# Sheet2.net
KiCad netlist of a schematic drawn in Altium Designer
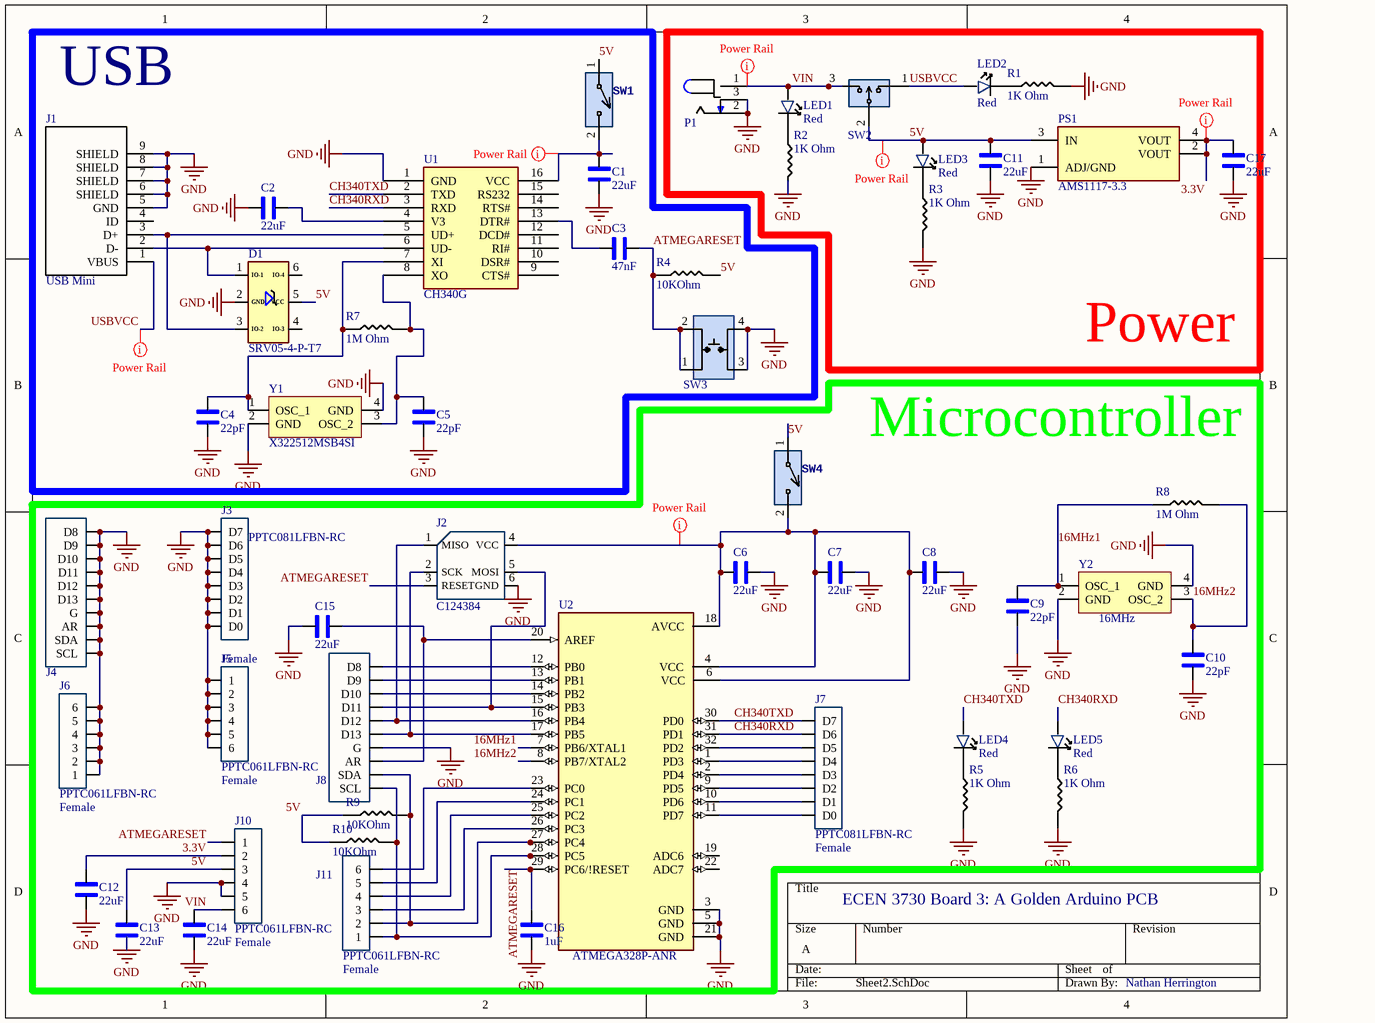
[diagram p0: Sheet2.SchDoc]

(export (version "E")
  (design (tool "Eeschema 10.0.6"))
  (components
    (comp (ref "C1")
      (value "22uF")
      (footprint "1206_Passive_Capacitor")
      (description "22uF ±10% 25V X5R 1206 Multilayer Ceramic Capacitors MLCC - SMD/SMT RoHS")
      (fields (field (name "MFR PART #") "CL31A226KAHNNNE") (field (name "LCSC PART#") "C12891"))
      (libsource (lib "ECEN5730Lib_2023_05_DS") (part "C_22uF_1206"))
    )
    (comp (ref "C2")
      (value "22uF")
      (footprint "1206_Passive_Capacitor")
      (description "22uF ±10% 25V X5R 1206 Multilayer Ceramic Capacitors MLCC - SMD/SMT RoHS")
      (fields (field (name "MFR PART #") "CL31A226KAHNNNE") (field (name "LCSC PART#") "C12891"))
      (libsource (lib "ECEN5730Lib_2023_05_DS") (part "C_22uF_1206"))
    )
    (comp (ref "C3")
      (value "47nF")
      (footprint "1206_Passive_Capacitor")
      (description "47nF ±5% 50V C0G 1206 Multilayer Ceramic Capacitors MLCC - SMD/SMT RoHS")
      (fields (field (name "LCSC PART#") "C21812") (field (name "MFR PART #") "GRM31M5C1H473JA01L"))
      (libsource (lib "ECEN5730Lib_2023_05_DS") (part "C_47nF_1206"))
    )
    (comp (ref "C4")
      (value "22pF")
      (footprint "1206_Passive_Capacitor")
      (description "22pF ±5% 1kV C0G 1206 Multilayer Ceramic Capacitors MLCC - SMD/SMT RoHS")
      (fields (field (name "MFR PART #") "CC1206JKNPOCBN220") (field (name "LCSC PART#") "C107174"))
      (libsource (lib "ECEN5730Lib_2023_05_DS") (part "C_22pF_1206"))
    )
    (comp (ref "C5")
      (value "22pF")
      (footprint "1206_Passive_Capacitor")
      (description "22pF ±5% 1kV C0G 1206 Multilayer Ceramic Capacitors MLCC - SMD/SMT RoHS")
      (fields (field (name "MFR PART #") "CC1206JKNPOCBN220") (field (name "LCSC PART#") "C107174"))
      (libsource (lib "ECEN5730Lib_2023_05_DS") (part "C_22pF_1206"))
    )
    (comp (ref "C6")
      (value "22uF")
      (footprint "1206_Passive_Capacitor")
      (description "22uF ±10% 25V X5R 1206 Multilayer Ceramic Capacitors MLCC - SMD/SMT RoHS")
      (fields (field (name "MFR PART #") "CL31A226KAHNNNE") (field (name "LCSC PART#") "C12891"))
      (libsource (lib "ECEN5730Lib_2023_05_DS") (part "C_22uF_1206"))
    )
    (comp (ref "C7")
      (value "22uF")
      (footprint "1206_Passive_Capacitor")
      (description "22uF ±10% 25V X5R 1206 Multilayer Ceramic Capacitors MLCC - SMD/SMT RoHS")
      (fields (field (name "MFR PART #") "CL31A226KAHNNNE") (field (name "LCSC PART#") "C12891"))
      (libsource (lib "ECEN5730Lib_2023_05_DS") (part "C_22uF_1206"))
    )
    (comp (ref "C8")
      (value "22uF")
      (footprint "1206_Passive_Capacitor")
      (description "22uF ±10% 25V X5R 1206 Multilayer Ceramic Capacitors MLCC - SMD/SMT RoHS")
      (fields (field (name "MFR PART #") "CL31A226KAHNNNE") (field (name "LCSC PART#") "C12891"))
      (libsource (lib "ECEN5730Lib_2023_05_DS") (part "C_22uF_1206"))
    )
    (comp (ref "C9")
      (value "22pF")
      (footprint "1206_Passive_Capacitor")
      (description "22pF ±5% 1kV C0G 1206 Multilayer Ceramic Capacitors MLCC - SMD/SMT RoHS")
      (fields (field (name "MFR PART #") "CC1206JKNPOCBN220") (field (name "LCSC PART#") "C107174"))
      (libsource (lib "ECEN5730Lib_2023_05_DS") (part "C_22pF_1206"))
    )
    (comp (ref "C10")
      (value "22pF")
      (footprint "1206_Passive_Capacitor")
      (description "22pF ±5% 1kV C0G 1206 Multilayer Ceramic Capacitors MLCC - SMD/SMT RoHS")
      (fields (field (name "MFR PART #") "CC1206JKNPOCBN220") (field (name "LCSC PART#") "C107174"))
      (libsource (lib "ECEN5730Lib_2023_05_DS") (part "C_22pF_1206"))
    )
    (comp (ref "C11")
      (value "22uF")
      (footprint "1206_Passive_Capacitor")
      (description "22uF ±10% 25V X5R 1206 Multilayer Ceramic Capacitors MLCC - SMD/SMT RoHS")
      (fields (field (name "MFR PART #") "CL31A226KAHNNNE") (field (name "LCSC PART#") "C12891"))
      (libsource (lib "ECEN5730Lib_2023_05_DS") (part "C_22uF_1206"))
    )
    (comp (ref "C12")
      (value "22uF")
      (footprint "1206_Passive_Capacitor")
      (description "22uF ±10% 25V X5R 1206 Multilayer Ceramic Capacitors MLCC - SMD/SMT RoHS")
      (fields (field (name "MFR PART #") "CL31A226KAHNNNE") (field (name "LCSC PART#") "C12891"))
      (libsource (lib "ECEN5730Lib_2023_05_DS") (part "C_22uF_1206"))
    )
    (comp (ref "C13")
      (value "22uF")
      (footprint "1206_Passive_Capacitor")
      (description "22uF ±10% 25V X5R 1206 Multilayer Ceramic Capacitors MLCC - SMD/SMT RoHS")
      (fields (field (name "MFR PART #") "CL31A226KAHNNNE") (field (name "LCSC PART#") "C12891"))
      (libsource (lib "ECEN5730Lib_2023_05_DS") (part "C_22uF_1206"))
    )
    (comp (ref "C14")
      (value "22uF")
      (footprint "1206_Passive_Capacitor")
      (description "22uF ±10% 25V X5R 1206 Multilayer Ceramic Capacitors MLCC - SMD/SMT RoHS")
      (fields (field (name "MFR PART #") "CL31A226KAHNNNE") (field (name "LCSC PART#") "C12891"))
      (libsource (lib "ECEN5730Lib_2023_05_DS") (part "C_22uF_1206"))
    )
    (comp (ref "C15")
      (value "22uF")
      (footprint "1206_Passive_Capacitor")
      (description "22uF ±10% 25V X5R 1206 Multilayer Ceramic Capacitors MLCC - SMD/SMT RoHS")
      (fields (field (name "MFR PART #") "CL31A226KAHNNNE") (field (name "LCSC PART#") "C12891"))
      (libsource (lib "ECEN5730Lib_2023_05_DS") (part "C_22uF_1206"))
    )
    (comp (ref "C16")
      (value "1uF")
      (footprint "1206_Passive_Capacitor")
      (description "MULTILAYER CERAMIC CAPACITORS MLCC - SMD/SMT 1UF 50V 1206 ROHS")
      (fields (field (name "MFR PART #") "CL31B105KBHNNNE") (field (name "LCSC PART#") "C1848"))
      (libsource (lib "ECEN5730Lib_2023_05_DS") (part "C_1uF_1206"))
    )
    (comp (ref "C17")
      (value "22uF")
      (footprint "1206_Passive_Capacitor")
      (description "22uF ±10% 25V X5R 1206 Multilayer Ceramic Capacitors MLCC - SMD/SMT RoHS")
      (fields (field (name "MFR PART #") "CL31A226KAHNNNE") (field (name "LCSC PART#") "C12891"))
      (libsource (lib "ECEN5730Lib_2023_05_DS") (part "C_22uF_1206"))
    )
    (comp (ref "D1")
      (value "SRV05-4-P-T7")
      (footprint "TVS")
      (description "TVS SOT-23-6 ROHS")
      (fields (field (name "LCSC PART#") "C85364"))
      (libsource (lib "ECEN5730Lib_2023_05_DS") (part "D_TVS_Diode"))
    )
    (comp (ref "J1")
      (value "USB Mini")
      (footprint "USB_MINI_B")
      (description "Through Hole USB Connectors RoHS")
      (fields (field (name "LCSC PART#") "C46398") (field (name "MFR PART #") "920-462A2021D10102"))
      (libsource (lib "ECEN5730Lib_2023_05_DS") (part "J_USB_B_Mini"))
    )
    (comp (ref "J2")
      (value "NRPN032PAEN-RC")
      (footprint "ICSP")
      (description "Connector Header Through Hole 6 position 0.079\" (2.00mm)")
      (fields (field (name "LCSC PART#") "C124384"))
      (libsource (lib "ECEN5730Lib_2023_05_DS") (part "J_ICSP"))
    )
    (comp (ref "J3")
      (value "PPTC081LFBN-RC")
      (footprint "8_PIN_ARD-DIG_100MIL")
      (description "8 Position Header Connector 0.100\" (2.54mm) Through Hole Tin")
      (fields (field (name "LCSC PART#") "C27438") (field (name "ALTIUM_VALUE") "Female"))
      (libsource (lib "ECEN5730Lib_2023_05_DS") (part "JF_8_PIN_FEMA_ARD-Dig"))
    )
    (comp (ref "J4")
      (value "PPTC101LFBN-RC")
      (footprint "10_PIN_ARDUINO_100MIL")
      (description "10 Position Header Connector 0.100\" (2.54mm) Through Hole Tin")
      (fields (field (name "LCSC PART#") "C225507"))
      (libsource (lib "ECEN5730Lib_2023_05_DS") (part "JF_10_PIN_FEMA_ARDUINO"))
    )
    (comp (ref "J5")
      (value "PPTC061LFBN-RC")
      (footprint "6_PIN_100MIL -Female")
      (description "6 Position Header Connector 0.100\" (2.54mm) Through Hole Tin")
      (fields (field (name "LCSC PART#") "C40877") (field (name "ALTIUM_VALUE") "Female"))
      (libsource (lib "ECEN5730Lib_2023_05_DS") (part "JF_6_PIN_FEMALE"))
    )
    (comp (ref "J6")
      (value "PPTC061LFBN-RC")
      (footprint "6_PIN_100MIL -Female")
      (description "6 Position Header Connector 0.100\" (2.54mm) Through Hole Tin")
      (fields (field (name "LCSC PART#") "C40877") (field (name "ALTIUM_VALUE") "Female"))
      (libsource (lib "") (part "JF_6_PIN_FEMALE_1"))
    )
    (comp (ref "J7")
      (value "PPTC081LFBN-RC")
      (footprint "8_PIN_ARD-DIG_100MIL")
      (description "8 Position Header Connector 0.100\" (2.54mm) Through Hole Tin")
      (fields (field (name "LCSC PART#") "C27438") (field (name "ALTIUM_VALUE") "Female"))
      (libsource (lib "ECEN5730Lib_2023_05_DS") (part "JF_8_PIN_FEMA_ARD-Dig"))
    )
    (comp (ref "J8")
      (value "PPTC101LFBN-RC")
      (footprint "10_PIN_ARDUINO_100MIL")
      (description "10 Position Header Connector 0.100\" (2.54mm) Through Hole Tin")
      (fields (field (name "LCSC PART#") "C225507"))
      (libsource (lib "ECEN5730Lib_2023_05_DS") (part "JF_10_PIN_FEMA_ARDUINO"))
    )
    (comp (ref "J10")
      (value "PPTC061LFBN-RC")
      (footprint "6_PIN_100MIL -Female")
      (description "6 Position Header Connector 0.100\" (2.54mm) Through Hole Tin")
      (fields (field (name "LCSC PART#") "C40877") (field (name "ALTIUM_VALUE") "Female"))
      (libsource (lib "ECEN5730Lib_2023_05_DS") (part "JF_6_PIN_FEMALE"))
    )
    (comp (ref "J11")
      (value "PPTC061LFBN-RC")
      (footprint "6_PIN_100MIL -Female")
      (description "6 Position Header Connector 0.100\" (2.54mm) Through Hole Tin")
      (fields (field (name "LCSC PART#") "C40877") (field (name "ALTIUM_VALUE") "Female"))
      (libsource (lib "") (part "JF_6_PIN_FEMALE_1"))
    )
    (comp (ref "LED1")
      (value "Red")
      (footprint "LED_1206")
      (description "Red 621~631nm 1206 Light Emitting Diodes (LED) RoHS")
      (fields (field (name "MFR PART #") "15-21/R6C-FQ1R1B/2T") (field (name "LCSC PART#") "C93133"))
      (libsource (lib "ECEN5730Lib_2023_05_DS") (part "LED_RED_1206"))
    )
    (comp (ref "LED2")
      (value "Red")
      (footprint "LED_1206")
      (description "Red 621~631nm 1206 Light Emitting Diodes (LED) RoHS")
      (fields (field (name "MFR PART #") "15-21/R6C-FQ1R1B/2T") (field (name "LCSC PART#") "C93133"))
      (libsource (lib "ECEN5730Lib_2023_05_DS") (part "LED_RED_1206"))
    )
    (comp (ref "LED3")
      (value "Red")
      (footprint "LED_1206")
      (description "Red 621~631nm 1206 Light Emitting Diodes (LED) RoHS")
      (fields (field (name "MFR PART #") "15-21/R6C-FQ1R1B/2T") (field (name "LCSC PART#") "C93133"))
      (libsource (lib "ECEN5730Lib_2023_05_DS") (part "LED_RED_1206"))
    )
    (comp (ref "LED4")
      (value "Red")
      (footprint "LED_1206")
      (description "Red 621~631nm 1206 Light Emitting Diodes (LED) RoHS")
      (fields (field (name "MFR PART #") "15-21/R6C-FQ1R1B/2T") (field (name "LCSC PART#") "C93133"))
      (libsource (lib "ECEN5730Lib_2023_05_DS") (part "LED_RED_1206"))
    )
    (comp (ref "LED5")
      (value "Red")
      (footprint "LED_1206")
      (description "Red 621~631nm 1206 Light Emitting Diodes (LED) RoHS")
      (fields (field (name "MFR PART #") "15-21/R6C-FQ1R1B/2T") (field (name "LCSC PART#") "C93133"))
      (libsource (lib "ECEN5730Lib_2023_05_DS") (part "LED_RED_1206"))
    )
    (comp (ref "P1")
      (value "Power Jack")
      (footprint "Power_Jack")
      (description "Power Barrel Connector Jack 2.10mm ID (0.083\"), 5.50mm OD (0.217\") Through Hole, Right Angle")
      (fields (field (name "MFR PART #") "PJ-102A") (field (name "LCSC PART#") "C136744"))
      (libsource (lib "ECEN5730Lib_2023_05_DS") (part "P_Power Jack"))
    )
    (comp (ref "PS1")
      (value "AMS1117-3.3")
      (footprint "LDO")
      (description "LOW DROPOUT REGULATORS(LDO) POSITIVE FIXED 1.3V @ 800MA 15V 3.3V 1A SOT-223 ROHS")
      (fields (field (name "LCSC PART#") "C6186"))
      (libsource (lib "ECEN5730Lib_2023_05_DS") (part "PS_AMS_LDO_3v3"))
    )
    (comp (ref "R1")
      (value "1K Ohm")
      (footprint "1206_Passive_Resitor")
      (description "CHIP RESISTOR - SURFACE MOUNT 1KOHMS ±1% 1/4W 1206 ROHS")
      (fields (field (name "MFR PART #") "RNCP1206FTD1K00CT") (field (name "LCSC PART#") "C4410"))
      (libsource (lib "ECEN5730Lib_2023_05_DS") (part "R_1K_1206"))
    )
    (comp (ref "R2")
      (value "1K Ohm")
      (footprint "1206_Passive_Resitor")
      (description "CHIP RESISTOR - SURFACE MOUNT 1KOHMS ±1% 1/4W 1206 ROHS")
      (fields (field (name "MFR PART #") "RNCP1206FTD1K00CT") (field (name "LCSC PART#") "C4410"))
      (libsource (lib "ECEN5730Lib_2023_05_DS") (part "R_1K_1206"))
    )
    (comp (ref "R3")
      (value "1K Ohm")
      (footprint "1206_Passive_Resitor")
      (description "CHIP RESISTOR - SURFACE MOUNT 1KOHMS ±1% 1/4W 1206 ROHS")
      (fields (field (name "MFR PART #") "RNCP1206FTD1K00CT") (field (name "LCSC PART#") "C4410"))
      (libsource (lib "ECEN5730Lib_2023_05_DS") (part "R_1K_1206"))
    )
    (comp (ref "R4")
      (value "10KOhm")
      (footprint "1206_Passive_Resitor")
      (description "10 kOhms ±5% 0.25W, 1/4W Chip Resistor 1206 (3216 Metric) Automotive AEC-Q200 Thick Film")
      (fields (field (name "MFR PART #") "RMCF1206FT10K0") (field (name "LCSC PART#") "C17902"))
      (libsource (lib "ECEN5730Lib_2023_05_DS") (part "R_10KOhm_1206"))
    )
    (comp (ref "R5")
      (value "1K Ohm")
      (footprint "1206_Passive_Resitor")
      (description "CHIP RESISTOR - SURFACE MOUNT 1KOHMS ±1% 1/4W 1206 ROHS")
      (fields (field (name "MFR PART #") "RNCP1206FTD1K00CT") (field (name "LCSC PART#") "C4410"))
      (libsource (lib "ECEN5730Lib_2023_05_DS") (part "R_1K_1206"))
    )
    (comp (ref "R6")
      (value "1K Ohm")
      (footprint "1206_Passive_Resitor")
      (description "CHIP RESISTOR - SURFACE MOUNT 1KOHMS ±1% 1/4W 1206 ROHS")
      (fields (field (name "MFR PART #") "RNCP1206FTD1K00CT") (field (name "LCSC PART#") "C4410"))
      (libsource (lib "ECEN5730Lib_2023_05_DS") (part "R_1K_1206"))
    )
    (comp (ref "R7")
      (value "1M Ohm")
      (footprint "1206_Passive_Resitor")
      (description "CHIP RESISTOR - SURFACE MOUNT 1MOHMS ±1% 1/4W 1206 ROHS")
      (fields (field (name "MFR PART #") "RMCF1206JT1M00") (field (name "LCSC PART#") "C17927"))
      (libsource (lib "ECEN5730Lib_2023_05_DS") (part "R_1M_1206"))
    )
    (comp (ref "R8")
      (value "1M Ohm")
      (footprint "1206_Passive_Resitor")
      (description "CHIP RESISTOR - SURFACE MOUNT 1MOHMS ±1% 1/4W 1206 ROHS")
      (fields (field (name "MFR PART #") "RMCF1206JT1M00") (field (name "LCSC PART#") "C17927"))
      (libsource (lib "ECEN5730Lib_2023_05_DS") (part "R_1M_1206"))
    )
    (comp (ref "R9")
      (value "10KOhm")
      (footprint "1206_Passive_Resitor")
      (description "10 kOhms ±5% 0.25W, 1/4W Chip Resistor 1206 (3216 Metric) Automotive AEC-Q200 Thick Film")
      (fields (field (name "MFR PART #") "RMCF1206FT10K0") (field (name "LCSC PART#") "C17902"))
      (libsource (lib "ECEN5730Lib_2023_05_DS") (part "R_10KOhm_1206"))
    )
    (comp (ref "R10")
      (value "10KOhm")
      (footprint "1206_Passive_Resitor")
      (description "10 kOhms ±5% 0.25W, 1/4W Chip Resistor 1206 (3216 Metric) Automotive AEC-Q200 Thick Film")
      (fields (field (name "MFR PART #") "RMCF1206FT10K0") (field (name "LCSC PART#") "C17902"))
      (libsource (lib "ECEN5730Lib_2023_05_DS") (part "R_10KOhm_1206"))
    )
    (comp (ref "SW1")
      (value "SW_2Pin_100mil_Switch")
      (footprint "2Pin-Header-Conn")
      (description "2Pin Header")
      (fields (field (name "LCSC PART#") "C124375"))
      (libsource (lib "ECEN5730Lib_2023_05_DS") (part "SW_2Pin_100mil_Switch"))
    )
    (comp (ref "SW2")
      (value "PREC003SAAN-RC")
      (footprint "3_PIN_100mil")
      (description "Connector Header Through Hole 3 position 0.100\" (2.54mm)")
      (fields (field (name "LCSC PART#") "C49257"))
      (libsource (lib "ECEN5730Lib_2023_05_DS") (part "SW_3Pin_100mil_Switch"))
    )
    (comp (ref "SW3")
      (value "TL3305AF160QG")
      (footprint "Switch_JLC")
      (description "Tactile Switch SPST-NO Top Actuated Surface Mount")
      (fields (field (name "MFR PART #") "KH-4.5X4.5X4.3H-STM") (field (name "LCSC PART#") "C2837550"))
      (libsource (lib "ECEN5730Lib_2023_05_DS") (part "SW_Push_Button_JLC"))
    )
    (comp (ref "SW4")
      (value "SW_2Pin_100mil_Switch")
      (footprint "2Pin-Header-Conn")
      (description "2Pin Header")
      (fields (field (name "LCSC PART#") "C124375"))
      (libsource (lib "ECEN5730Lib_2023_05_DS") (part "SW_2Pin_100mil_Switch"))
    )
    (comp (ref "U1")
      (value "CH340G")
      (footprint "USB to serial")
      (description "Transceiver USB 2.0 2Mbps SOP-16_150mil USB ICs RoHS")
      (fields (field (name "LCSC PART#") "C14267"))
      (libsource (lib "ECEN5730Lib_2023_05_DS") (part "U_USBtoSerial"))
    )
    (comp (ref "U2")
      (value "ATMEGA328P-ANR")
      (footprint "ATMega328P")
      (description "AVR AVR® ATmega Microcontroller IC 8-Bit 20MHz 32KB (16K x 16) FLASH 32-TQFP (7x7)")
      (fields (field (name "MFR PART #") "ATMEGA328P-AU") (field (name "LCSC PART#") "C14877"))
      (libsource (lib "ECEN5730Lib_2023_05_DS") (part "U_ATMega328P"))
    )
    (comp (ref "Y1")
      (value "X322512MSB4SI")
      (footprint "Crystal resonator")
      (description "SMD Crystal Resonators 12MHz ±10ppm SMD-3225_4P RoHS")
      (fields (field (name "LCSC PART#") "C9002"))
      (libsource (lib "ECEN5730Lib_2023_05_DS") (part "X_12MHz_Res"))
    )
    (comp (ref "Y2")
      (value "16MHz")
      (footprint "Crystal resonator")
      (description "±10ppm 16000000Hz -40℃~85℃ 贴片无源晶振 60Ω 9pF SMD3225-4P Crystals ROHS")
      (fields (field (name "LCSC PART#") "C13738") (field (name "MFR PART #") "X322516MLB4SI"))
      (libsource (lib "ECEN5730Lib_2023_05_DS") (part "X_16Mhz_Res"))
    )
  )
  (nets
    (net (code "1") (name "/3.3V") (class "Default")
      (node (ref "C12") (pin "1") (pinfunction "1_1") (pintype "passive"))
      (node (ref "C17") (pin "2") (pinfunction "2_2") (pintype "passive"))
      (node (ref "J10") (pin "2") (pinfunction "2_2") (pintype "passive"))
      (node (ref "PS1") (pin "2") (pinfunction "VOUT_2") (pintype "power_in"))
      (node (ref "PS1") (pin "4") (pinfunction "VOUT_4") (pintype "power_in"))
    )
    (net (code "2") (name "/5V") (class "Default")
      (node (ref "C11") (pin "2") (pinfunction "2_2") (pintype "passive"))
      (node (ref "C13") (pin "1") (pinfunction "1_1") (pintype "passive"))
      (node (ref "D1") (pin "5") (pinfunction "VCC_5") (pintype "passive"))
      (node (ref "J10") (pin "3") (pinfunction "3_3") (pintype "passive"))
      (node (ref "LED3") (pin "1") (pinfunction "1_1") (pintype "passive"))
      (node (ref "PS1") (pin "3") (pinfunction "IN_3") (pintype "power_in"))
      (node (ref "R10") (pin "1") (pinfunction "1_1") (pintype "passive"))
      (node (ref "R4") (pin "2") (pinfunction "2_2") (pintype "passive"))
      (node (ref "R9") (pin "1") (pinfunction "1_1") (pintype "passive"))
      (node (ref "SW1") (pin "1") (pinfunction "1_1") (pintype "passive"))
      (node (ref "SW2") (pin "2") (pinfunction "2_2") (pintype "passive"))
      (node (ref "SW4") (pin "1") (pinfunction "1_1") (pintype "passive"))
    )
    (net (code "3") (name "/16MHz1") (class "Default")
      (node (ref "C9") (pin "1") (pinfunction "1_1") (pintype "passive"))
      (node (ref "R8") (pin "1") (pinfunction "1_1") (pintype "passive"))
      (node (ref "U2") (pin "7") (pinfunction "PB6/XTAL1_7") (pintype "bidirectional"))
      (node (ref "Y2") (pin "1") (pinfunction "OSC_1_1") (pintype "passive"))
    )
    (net (code "4") (name "/16MHz2") (class "Default")
      (node (ref "C10") (pin "1") (pinfunction "1_1") (pintype "passive"))
      (node (ref "R8") (pin "2") (pinfunction "2_2") (pintype "passive"))
      (node (ref "U2") (pin "8") (pinfunction "PB7/XTAL2_8") (pintype "bidirectional"))
      (node (ref "Y2") (pin "3") (pinfunction "OSC_2_3") (pintype "passive"))
    )
    (net (code "5") (name "/ATMEGARESET") (class "Default")
      (node (ref "C16") (pin "1") (pinfunction "1_1") (pintype "passive"))
      (node (ref "C3") (pin "2") (pinfunction "2_2") (pintype "passive"))
      (node (ref "J10") (pin "1") (pinfunction "1_1") (pintype "passive"))
      (node (ref "J2") (pin "3") (pinfunction "RESET_3") (pintype "passive"))
      (node (ref "R4") (pin "1") (pinfunction "1_1") (pintype "passive"))
      (node (ref "SW3") (pin "1") (pinfunction "1_1") (pintype "passive"))
      (node (ref "SW3") (pin "2") (pinfunction "2_2") (pintype "passive"))
      (node (ref "U2") (pin "29") (pinfunction "PC6/!RESET_29") (pintype "bidirectional"))
    )
    (net (code "6") (name "/CH340RXD") (class "Default")
      (node (ref "J7") (pin "2") (pinfunction "D6_2") (pintype "passive"))
      (node (ref "LED5") (pin "1") (pinfunction "1_1") (pintype "passive"))
      (node (ref "U1") (pin "3") (pinfunction "RXD_3") (pintype "passive"))
      (node (ref "U2") (pin "31") (pinfunction "PD1_31") (pintype "bidirectional"))
    )
    (net (code "7") (name "/CH340TXD") (class "Default")
      (node (ref "J7") (pin "1") (pinfunction "D7_1") (pintype "passive"))
      (node (ref "LED4") (pin "1") (pinfunction "1_1") (pintype "passive"))
      (node (ref "U1") (pin "2") (pinfunction "TXD_2") (pintype "passive"))
      (node (ref "U2") (pin "30") (pinfunction "PD0_30") (pintype "bidirectional"))
    )
    (net (code "8") (name "/USBVCC") (class "Default")
      (node (ref "J1") (pin "1") (pinfunction "VBUS_1") (pintype "passive"))
      (node (ref "LED2") (pin "1") (pinfunction "1_1") (pintype "passive"))
      (node (ref "SW2") (pin "1") (pinfunction "1_1") (pintype "passive"))
    )
    (net (code "9") (name "/VIN") (class "Default")
      (node (ref "C14") (pin "2") (pinfunction "2_2") (pintype "passive"))
      (node (ref "J10") (pin "6") (pinfunction "6_6") (pintype "passive"))
      (node (ref "LED1") (pin "1") (pinfunction "1_1") (pintype "passive"))
      (node (ref "P1") (pin "1") (pinfunction "1_1") (pintype "power_in"))
      (node (ref "SW2") (pin "3") (pinfunction "3_3") (pintype "passive"))
    )
    (net (code "10") (name "GND") (class "Default")
      (node (ref "C1") (pin "2") (pinfunction "2_2") (pintype "passive"))
      (node (ref "C10") (pin "2") (pinfunction "2_2") (pintype "passive"))
      (node (ref "C11") (pin "1") (pinfunction "1_1") (pintype "passive"))
      (node (ref "C12") (pin "2") (pinfunction "2_2") (pintype "passive"))
      (node (ref "C13") (pin "2") (pinfunction "2_2") (pintype "passive"))
      (node (ref "C14") (pin "1") (pinfunction "1_1") (pintype "passive"))
      (node (ref "C15") (pin "1") (pinfunction "1_1") (pintype "passive"))
      (node (ref "C16") (pin "2") (pinfunction "2_2") (pintype "passive"))
      (node (ref "C17") (pin "1") (pinfunction "1_1") (pintype "passive"))
      (node (ref "C2") (pin "1") (pinfunction "1_1") (pintype "passive"))
      (node (ref "C4") (pin "1") (pinfunction "1_1") (pintype "passive"))
      (node (ref "C5") (pin "1") (pinfunction "1_1") (pintype "passive"))
      (node (ref "C6") (pin "2") (pinfunction "2_2") (pintype "passive"))
      (node (ref "C7") (pin "2") (pinfunction "2_2") (pintype "passive"))
      (node (ref "C8") (pin "2") (pinfunction "2_2") (pintype "passive"))
      (node (ref "C9") (pin "2") (pinfunction "2_2") (pintype "passive"))
      (node (ref "D1") (pin "2") (pinfunction "GND_2") (pintype "passive"))
      (node (ref "J1") (pin "5") (pinfunction "GND_5") (pintype "passive"))
      (node (ref "J1") (pin "6") (pinfunction "SHIELD_6") (pintype "passive"))
      (node (ref "J1") (pin "7") (pinfunction "SHIELD_7") (pintype "passive"))
      (node (ref "J1") (pin "8") (pinfunction "SHIELD_8") (pintype "passive"))
      (node (ref "J1") (pin "9") (pinfunction "SHIELD_9") (pintype "passive"))
      (node (ref "J10") (pin "4") (pinfunction "4_4") (pintype "passive"))
      (node (ref "J10") (pin "5") (pinfunction "5_5") (pintype "passive"))
      (node (ref "J2") (pin "6") (pinfunction "GND_6") (pintype "passive"))
      (node (ref "J3") (pin "1") (pinfunction "D7_1") (pintype "passive"))
      (node (ref "J3") (pin "2") (pinfunction "D6_2") (pintype "passive"))
      (node (ref "J3") (pin "3") (pinfunction "D5_3") (pintype "passive"))
      (node (ref "J3") (pin "4") (pinfunction "D4_4") (pintype "passive"))
      (node (ref "J3") (pin "5") (pinfunction "D3_5") (pintype "passive"))
      (node (ref "J3") (pin "6") (pinfunction "D2_6") (pintype "passive"))
      (node (ref "J3") (pin "7") (pinfunction "D1_7") (pintype "passive"))
      (node (ref "J3") (pin "8") (pinfunction "D0_8") (pintype "passive"))
      (node (ref "J4") (pin "1") (pinfunction "SCL_1") (pintype "passive"))
      (node (ref "J4") (pin "10") (pinfunction "D8_10") (pintype "passive"))
      (node (ref "J4") (pin "2") (pinfunction "SDA_2") (pintype "passive"))
      (node (ref "J4") (pin "3") (pinfunction "AR_3") (pintype "passive"))
      (node (ref "J4") (pin "4") (pinfunction "G_4") (pintype "passive"))
      (node (ref "J4") (pin "5") (pinfunction "D13_5") (pintype "passive"))
      (node (ref "J4") (pin "6") (pinfunction "D12_6") (pintype "passive"))
      (node (ref "J4") (pin "7") (pinfunction "D11_7") (pintype "passive"))
      (node (ref "J4") (pin "8") (pinfunction "D10_8") (pintype "passive"))
      (node (ref "J4") (pin "9") (pinfunction "D9_9") (pintype "passive"))
      (node (ref "J5") (pin "1") (pinfunction "1_1") (pintype "passive"))
      (node (ref "J5") (pin "2") (pinfunction "2_2") (pintype "passive"))
      (node (ref "J5") (pin "3") (pinfunction "3_3") (pintype "passive"))
      (node (ref "J5") (pin "4") (pinfunction "4_4") (pintype "passive"))
      (node (ref "J5") (pin "5") (pinfunction "5_5") (pintype "passive"))
      (node (ref "J5") (pin "6") (pinfunction "6_6") (pintype "passive"))
      (node (ref "J6") (pin "1") (pinfunction "1_1") (pintype "passive"))
      (node (ref "J6") (pin "2") (pinfunction "2_2") (pintype "passive"))
      (node (ref "J6") (pin "3") (pinfunction "3_3") (pintype "passive"))
      (node (ref "J6") (pin "4") (pinfunction "4_4") (pintype "passive"))
      (node (ref "J6") (pin "5") (pinfunction "5_5") (pintype "passive"))
      (node (ref "J6") (pin "6") (pinfunction "6_6") (pintype "passive"))
      (node (ref "J8") (pin "4") (pinfunction "G_4") (pintype "passive"))
      (node (ref "P1") (pin "2") (pinfunction "2_2") (pintype "power_in"))
      (node (ref "P1") (pin "3") (pinfunction "3_3") (pintype "power_in"))
      (node (ref "PS1") (pin "1") (pinfunction "ADJ/GND_1") (pintype "passive"))
      (node (ref "R1") (pin "2") (pinfunction "2_2") (pintype "passive"))
      (node (ref "R2") (pin "2") (pinfunction "2_2") (pintype "passive"))
      (node (ref "R3") (pin "2") (pinfunction "2_2") (pintype "passive"))
      (node (ref "R5") (pin "2") (pinfunction "2_2") (pintype "passive"))
      (node (ref "R6") (pin "2") (pinfunction "2_2") (pintype "passive"))
      (node (ref "SW3") (pin "3") (pinfunction "3_3") (pintype "passive"))
      (node (ref "SW3") (pin "4") (pinfunction "4_4") (pintype "passive"))
      (node (ref "U1") (pin "1") (pinfunction "GND_1") (pintype "passive"))
      (node (ref "U2") (pin "21") (pinfunction "GND_21") (pintype "power_in"))
      (node (ref "U2") (pin "3") (pinfunction "GND_3") (pintype "power_in"))
      (node (ref "U2") (pin "5") (pinfunction "GND_5") (pintype "power_in"))
      (node (ref "Y1") (pin "2") (pinfunction "GND_2") (pintype "passive"))
      (node (ref "Y1") (pin "4") (pinfunction "GND_4") (pintype "passive"))
      (node (ref "Y2") (pin "2") (pinfunction "GND_2") (pintype "passive"))
      (node (ref "Y2") (pin "4") (pinfunction "GND_4") (pintype "passive"))
    )
    (net (code "11") (name "Net-(D1-IO-1)") (class "Default")
      (node (ref "D1") (pin "1") (pinfunction "IO-1_1") (pintype "passive"))
      (node (ref "J1") (pin "2") (pinfunction "D-_2") (pintype "passive"))
      (node (ref "U1") (pin "6") (pinfunction "UD-_6") (pintype "passive"))
    )
    (net (code "12") (name "Net-(D1-IO-2)") (class "Default")
      (node (ref "D1") (pin "3") (pinfunction "IO-2_3") (pintype "passive"))
      (node (ref "J1") (pin "3") (pinfunction "D+_3") (pintype "passive"))
      (node (ref "U1") (pin "5") (pinfunction "UD+_5") (pintype "passive"))
    )
    (net (code "13") (name "Net-(J2-MISO)") (class "Default")
      (node (ref "J2") (pin "1") (pinfunction "MISO_1") (pintype "passive"))
      (node (ref "J8") (pin "6") (pinfunction "D12_6") (pintype "passive"))
      (node (ref "U2") (pin "16") (pinfunction "PB4_16") (pintype "bidirectional"))
    )
    (net (code "14") (name "Net-(J2-MOSI)") (class "Default")
      (node (ref "J2") (pin "5") (pinfunction "MOSI_5") (pintype "passive"))
      (node (ref "J8") (pin "7") (pinfunction "D11_7") (pintype "passive"))
      (node (ref "U2") (pin "15") (pinfunction "PB3_15") (pintype "bidirectional"))
    )
    (net (code "15") (name "Net-(J2-SCK)") (class "Default")
      (node (ref "J2") (pin "2") (pinfunction "SCK_2") (pintype "passive"))
      (node (ref "J8") (pin "5") (pinfunction "D13_5") (pintype "passive"))
      (node (ref "U2") (pin "17") (pinfunction "PB5_17") (pintype "bidirectional"))
    )
    (net (code "16") (name "Net-(J2-VCC)") (class "Default")
      (node (ref "C6") (pin "1") (pinfunction "1_1") (pintype "passive"))
      (node (ref "C7") (pin "1") (pinfunction "1_1") (pintype "passive"))
      (node (ref "C8") (pin "1") (pinfunction "1_1") (pintype "passive"))
      (node (ref "J2") (pin "4") (pinfunction "VCC_4") (pintype "passive"))
      (node (ref "SW4") (pin "2") (pinfunction "2_2") (pintype "passive"))
      (node (ref "U2") (pin "18") (pinfunction "AVCC_18") (pintype "power_in"))
      (node (ref "U2") (pin "4") (pinfunction "VCC_4") (pintype "power_in"))
      (node (ref "U2") (pin "6") (pinfunction "VCC_6") (pintype "power_in"))
    )
    (net (code "17") (name "Net-(J7-D0)") (class "Default")
      (node (ref "J7") (pin "8") (pinfunction "D0_8") (pintype "passive"))
      (node (ref "U2") (pin "11") (pinfunction "PD7_11") (pintype "bidirectional"))
    )
    (net (code "18") (name "Net-(J7-D1)") (class "Default")
      (node (ref "J7") (pin "7") (pinfunction "D1_7") (pintype "passive"))
      (node (ref "U2") (pin "10") (pinfunction "PD6_10") (pintype "bidirectional"))
    )
    (net (code "19") (name "Net-(J7-D2)") (class "Default")
      (node (ref "J7") (pin "6") (pinfunction "D2_6") (pintype "passive"))
      (node (ref "U2") (pin "9") (pinfunction "PD5_9") (pintype "bidirectional"))
    )
    (net (code "20") (name "Net-(J7-D3)") (class "Default")
      (node (ref "J7") (pin "5") (pinfunction "D3_5") (pintype "passive"))
      (node (ref "U2") (pin "2") (pinfunction "PD4_2") (pintype "bidirectional"))
    )
    (net (code "21") (name "Net-(J7-D4)") (class "Default")
      (node (ref "J7") (pin "4") (pinfunction "D4_4") (pintype "passive"))
      (node (ref "U2") (pin "1") (pinfunction "PD3_1") (pintype "bidirectional"))
    )
    (net (code "22") (name "Net-(J7-D5)") (class "Default")
      (node (ref "J7") (pin "3") (pinfunction "D5_3") (pintype "passive"))
      (node (ref "U2") (pin "32") (pinfunction "PD2_32") (pintype "bidirectional"))
    )
    (net (code "23") (name "Net-(J8-AR)") (class "Default")
      (node (ref "C15") (pin "2") (pinfunction "2_2") (pintype "passive"))
      (node (ref "J8") (pin "3") (pinfunction "AR_3") (pintype "passive"))
      (node (ref "U2") (pin "20") (pinfunction "AREF_20") (pintype "input"))
    )
    (net (code "24") (name "Net-(J8-D8)") (class "Default")
      (node (ref "J8") (pin "10") (pinfunction "D8_10") (pintype "passive"))
      (node (ref "U2") (pin "12") (pinfunction "PB0_12") (pintype "bidirectional"))
    )
    (net (code "25") (name "Net-(J8-D9)") (class "Default")
      (node (ref "J8") (pin "9") (pinfunction "D9_9") (pintype "passive"))
      (node (ref "U2") (pin "13") (pinfunction "PB1_13") (pintype "bidirectional"))
    )
    (net (code "26") (name "Net-(J8-D10)") (class "Default")
      (node (ref "J8") (pin "8") (pinfunction "D10_8") (pintype "passive"))
      (node (ref "U2") (pin "14") (pinfunction "PB2_14") (pintype "bidirectional"))
    )
    (net (code "27") (name "Net-(J8-SCL)") (class "Default")
      (node (ref "J11") (pin "1") (pinfunction "1_1") (pintype "passive"))
      (node (ref "J8") (pin "1") (pinfunction "SCL_1") (pintype "passive"))
      (node (ref "R10") (pin "2") (pinfunction "2_2") (pintype "passive"))
      (node (ref "U2") (pin "28") (pinfunction "PC5_28") (pintype "bidirectional"))
    )
    (net (code "28") (name "Net-(J8-SDA)") (class "Default")
      (node (ref "J11") (pin "2") (pinfunction "2_2") (pintype "passive"))
      (node (ref "J8") (pin "2") (pinfunction "SDA_2") (pintype "passive"))
      (node (ref "R9") (pin "2") (pinfunction "2_2") (pintype "passive"))
      (node (ref "U2") (pin "27") (pinfunction "PC4_27") (pintype "bidirectional"))
    )
    (net (code "29") (name "Net-(LED1-Pad2)") (class "Default")
      (node (ref "LED1") (pin "2") (pinfunction "2_2") (pintype "passive"))
      (node (ref "R2") (pin "1") (pinfunction "1_1") (pintype "passive"))
    )
    (net (code "30") (name "Net-(LED2-Pad2)") (class "Default")
      (node (ref "LED2") (pin "2") (pinfunction "2_2") (pintype "passive"))
      (node (ref "R1") (pin "1") (pinfunction "1_1") (pintype "passive"))
    )
    (net (code "31") (name "Net-(LED3-Pad2)") (class "Default")
      (node (ref "LED3") (pin "2") (pinfunction "2_2") (pintype "passive"))
      (node (ref "R3") (pin "1") (pinfunction "1_1") (pintype "passive"))
    )
    (net (code "32") (name "Net-(LED4-Pad2)") (class "Default")
      (node (ref "LED4") (pin "2") (pinfunction "2_2") (pintype "passive"))
      (node (ref "R5") (pin "1") (pinfunction "1_1") (pintype "passive"))
    )
    (net (code "33") (name "Net-(LED5-Pad2)") (class "Default")
      (node (ref "LED5") (pin "2") (pinfunction "2_2") (pintype "passive"))
      (node (ref "R6") (pin "1") (pinfunction "1_1") (pintype "passive"))
    )
    (net (code "34") (name "Net-(U1-DTR#)") (class "Default")
      (node (ref "C3") (pin "1") (pinfunction "1_1") (pintype "passive"))
      (node (ref "U1") (pin "13") (pinfunction "DTR#_13") (pintype "passive"))
    )
    (net (code "35") (name "Net-(U1-V3)") (class "Default")
      (node (ref "C2") (pin "2") (pinfunction "2_2") (pintype "passive"))
      (node (ref "U1") (pin "4") (pinfunction "V3_4") (pintype "passive"))
    )
    (net (code "36") (name "Net-(U1-VCC)") (class "Default")
      (node (ref "C1") (pin "1") (pinfunction "1_1") (pintype "passive"))
      (node (ref "SW1") (pin "2") (pinfunction "2_2") (pintype "passive"))
      (node (ref "U1") (pin "16") (pinfunction "VCC_16") (pintype "passive"))
    )
    (net (code "37") (name "Net-(U1-XI)") (class "Default")
      (node (ref "C4") (pin "2") (pinfunction "2_2") (pintype "passive"))
      (node (ref "R7") (pin "1") (pinfunction "1_1") (pintype "passive"))
      (node (ref "U1") (pin "7") (pinfunction "XI_7") (pintype "passive"))
      (node (ref "Y1") (pin "1") (pinfunction "OSC_1_1") (pintype "passive"))
    )
    (net (code "38") (name "Net-(U1-XO)") (class "Default")
      (node (ref "C5") (pin "2") (pinfunction "2_2") (pintype "passive"))
      (node (ref "R7") (pin "2") (pinfunction "2_2") (pintype "passive"))
      (node (ref "U1") (pin "8") (pinfunction "XO_8") (pintype "passive"))
      (node (ref "Y1") (pin "3") (pinfunction "OSC_2_3") (pintype "passive"))
    )
    (net (code "39") (name "Net-(U2-PC0)") (class "Default")
      (node (ref "J11") (pin "6") (pinfunction "6_6") (pintype "passive"))
      (node (ref "U2") (pin "23") (pinfunction "PC0_23") (pintype "bidirectional"))
    )
    (net (code "40") (name "Net-(U2-PC1)") (class "Default")
      (node (ref "J11") (pin "5") (pinfunction "5_5") (pintype "passive"))
      (node (ref "U2") (pin "24") (pinfunction "PC1_24") (pintype "bidirectional"))
    )
    (net (code "41") (name "Net-(U2-PC2)") (class "Default")
      (node (ref "J11") (pin "4") (pinfunction "4_4") (pintype "passive"))
      (node (ref "U2") (pin "25") (pinfunction "PC2_25") (pintype "bidirectional"))
    )
    (net (code "42") (name "Net-(U2-PC3)") (class "Default")
      (node (ref "J11") (pin "3") (pinfunction "3_3") (pintype "passive"))
      (node (ref "U2") (pin "26") (pinfunction "PC3_26") (pintype "bidirectional"))
    )
    (net (code "43") (name "unconnected-(D1-IO-3-Pad4)") (class "Default")
      (node (ref "D1") (pin "4") (pinfunction "IO-3_4") (pintype "passive"))
    )
    (net (code "44") (name "unconnected-(D1-IO-4-Pad6)") (class "Default")
      (node (ref "D1") (pin "6") (pinfunction "IO-4_6") (pintype "passive"))
    )
    (net (code "45") (name "unconnected-(J1-ID-Pad4)") (class "Default")
      (node (ref "J1") (pin "4") (pinfunction "ID_4") (pintype "passive"))
    )
    (net (code "46") (name "unconnected-(U1-CTS#-Pad9)") (class "Default")
      (node (ref "U1") (pin "9") (pinfunction "CTS#_9") (pintype "passive"))
    )
    (net (code "47") (name "unconnected-(U1-DCD#-Pad12)") (class "Default")
      (node (ref "U1") (pin "12") (pinfunction "DCD#_12") (pintype "passive"))
    )
    (net (code "48") (name "unconnected-(U1-DSR#-Pad10)") (class "Default")
      (node (ref "U1") (pin "10") (pinfunction "DSR#_10") (pintype "passive"))
    )
    (net (code "49") (name "unconnected-(U1-RI#-Pad11)") (class "Default")
      (node (ref "U1") (pin "11") (pinfunction "RI#_11") (pintype "passive"))
    )
    (net (code "50") (name "unconnected-(U1-RS232-Pad15)") (class "Default")
      (node (ref "U1") (pin "15") (pinfunction "RS232_15") (pintype "passive"))
    )
    (net (code "51") (name "unconnected-(U1-RTS#-Pad14)") (class "Default")
      (node (ref "U1") (pin "14") (pinfunction "RTS#_14") (pintype "passive"))
    )
    (net (code "52") (name "unconnected-(U2-ADC6-Pad19)") (class "Default")
      (node (ref "U2") (pin "19") (pinfunction "ADC6_19") (pintype "bidirectional"))
    )
    (net (code "53") (name "unconnected-(U2-ADC7-Pad22)") (class "Default")
      (node (ref "U2") (pin "22") (pinfunction "ADC7_22") (pintype "bidirectional"))
    )
  )
)
